# SCH_ZX-WiFi_2025-09-04.net
KiCad netlist of a schematic drawn in EasyEDA
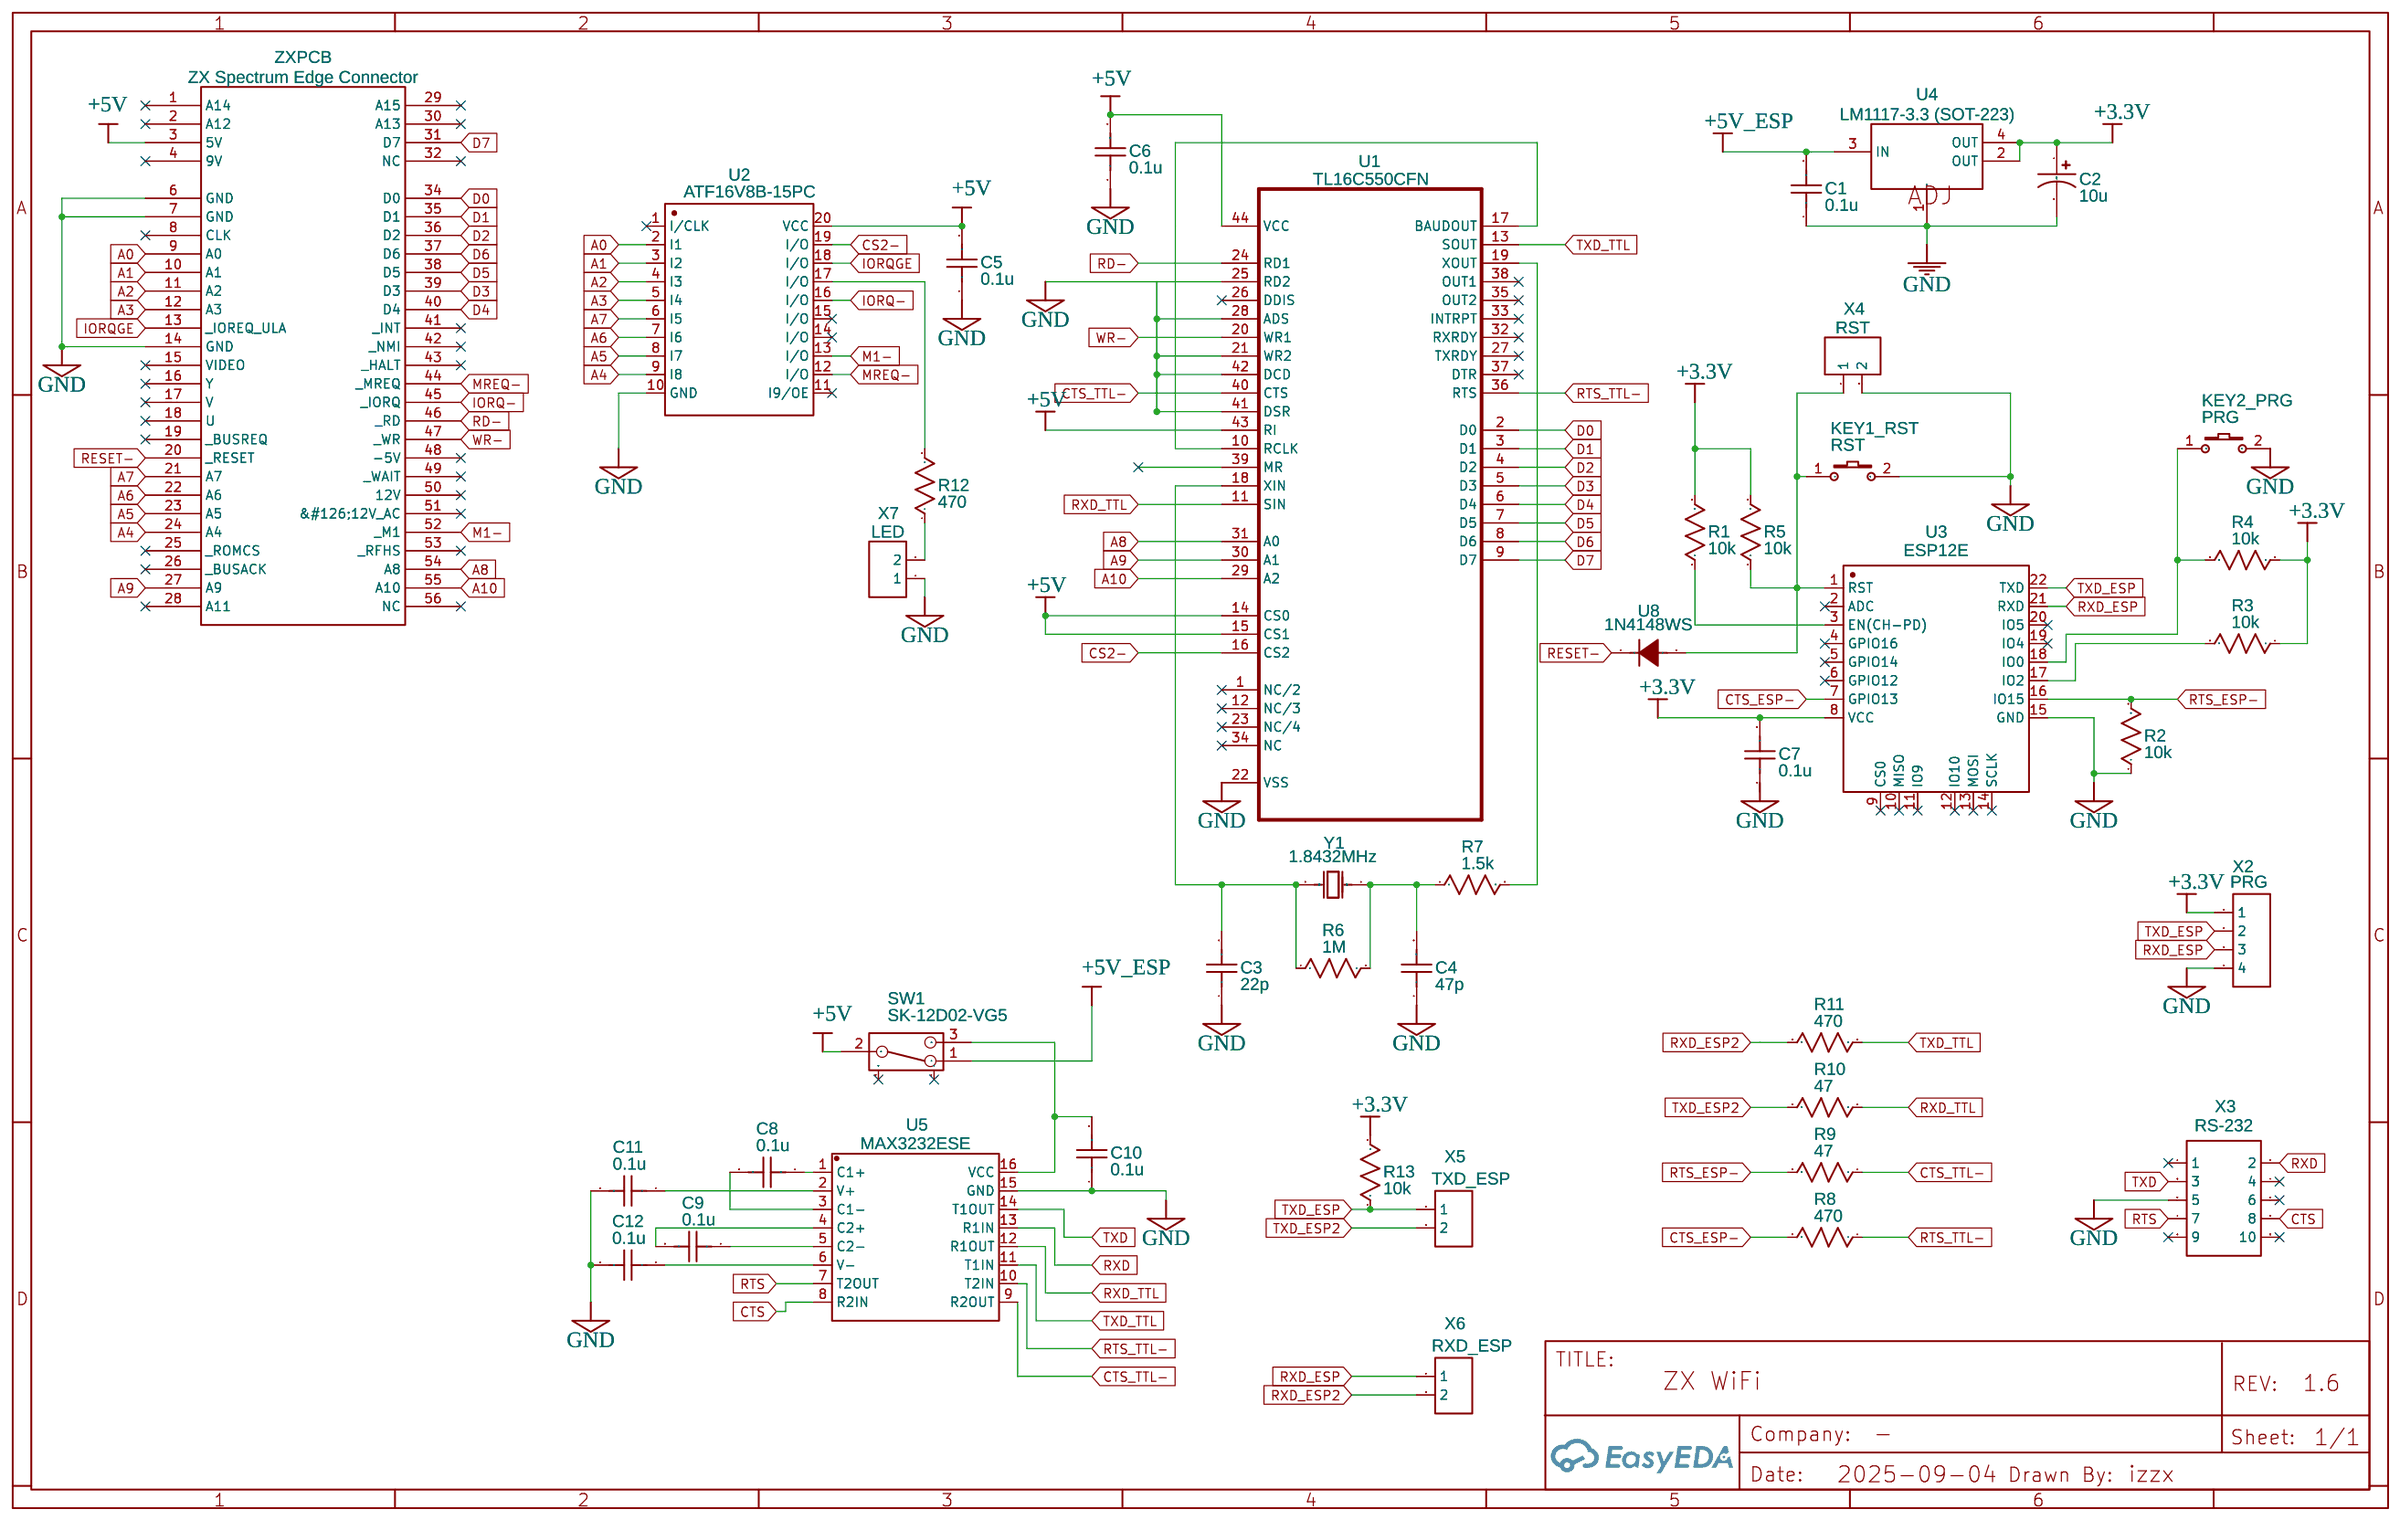
[diagram p0: schematic sheet]

(export (version "E")
  (design (tool "Eeschema 10.0.6"))
  (components
    (comp (ref "C1") (value "0.1u") (libsource (lib "") (part "C_0805_US_1")))
    (comp (ref "C2") (value "10u") (libsource (lib "") (part "C_Tan_SMD_A_US")))
    (comp (ref "C3") (value "22p") (libsource (lib "") (part "C_0805_US_1")))
    (comp (ref "C4") (value "47p") (libsource (lib "") (part "C_0805_US_1")))
    (comp (ref "C5") (value "0.1u") (libsource (lib "") (part "C_0805_US_1")))
    (comp (ref "C6") (value "0.1u") (libsource (lib "") (part "C_0805_US_1")))
    (comp (ref "C7") (value "0.1u") (libsource (lib "") (part "C_0805_US_1")))
    (comp (ref "C8") (value "0.1u") (libsource (lib "") (part "C_0805_US")))
    (comp (ref "C9") (value "0.1u") (libsource (lib "") (part "C_0805_US")))
    (comp (ref "C10") (value "0.1u") (libsource (lib "") (part "C_0805_US_1")))
    (comp (ref "C11") (value "0.1u") (libsource (lib "") (part "C_0805_US")))
    (comp (ref "C12") (value "0.1u") (libsource (lib "") (part "C_0805_US")))
    (comp (ref "KEY1_RST")
      (value "RST")
      (fields (field (name "Manufacturer Part") "K2-1107ST-A4SW-06"))
      (libsource (lib "") (part "K2-3.6×6.1_SMD"))
    )
    (comp (ref "KEY2_PRG")
      (value "PRG")
      (fields (field (name "Manufacturer Part") "K2-1107ST-A4SW-06"))
      (libsource (lib "") (part "K2-3.6×6.1_SMD_1"))
    )
    (comp (ref "R1") (value "10k") (libsource (lib "") (part "R_0805_US_1")))
    (comp (ref "R2") (value "10k") (libsource (lib "") (part "R_0805_US_1")))
    (comp (ref "R3") (value "10k") (libsource (lib "") (part "R_0805_US")))
    (comp (ref "R4") (value "10k") (libsource (lib "") (part "R_0805_US")))
    (comp (ref "R5") (value "10k") (libsource (lib "") (part "R_0805_US_1")))
    (comp (ref "R6") (value "1M") (libsource (lib "") (part "R_0805_US_2")))
    (comp (ref "R7") (value "1.5k") (libsource (lib "") (part "R_0805_US_2")))
    (comp (ref "R8") (value "470") (libsource (lib "") (part "R_0805_US")))
    (comp (ref "R9") (value "47") (libsource (lib "") (part "R_0805_US")))
    (comp (ref "R10") (value "47") (libsource (lib "") (part "R_0805_US")))
    (comp (ref "R11") (value "470") (libsource (lib "") (part "R_0805_US")))
    (comp (ref "R12") (value "470") (libsource (lib "") (part "R_0805_US_1")))
    (comp (ref "R13") (value "10k") (libsource (lib "") (part "R_0805_US_1")))
    (comp (ref "SW1")
      (value "SK-12D02-VG5")
      (fields (field (name "Manufacturer") "Rectangular Connectors - Contacts"))
      (libsource (lib "") (part "SK-12D02-VG5"))
    )
    (comp (ref "U1") (value "TL16C550CFN") (libsource (lib "") (part "TL16C550CFN")))
    (comp (ref "U2")
      (value "ATF16V8B-15PC")
      (fields
        (field (name "Manufacturer Part") "ATF16V8B-15PU")
        (field (name "Manufacturer") "MICROCHIP(美国微芯)")
      )
      (libsource (lib "") (part "ATF16V8B-15PU"))
    )
    (comp (ref "U3") (value "ESP12E") (libsource (lib "") (part "ESP12E/F")))
    (comp (ref "U4")
      (value "LM1117-3.3 (SOT-223)")
      (fields (field (name "Manufacturer Part") "LM317G-AA3-R") (field (name "Manufacturer") "UTC"))
      (libsource (lib "") (part "LM317(SOT-223)"))
    )
    (comp (ref "U5")
      (value "MAX3232ESE")
      (fields (field (name "Manufacturer") "UMW(友台半导体)"))
      (libsource (lib "") (part "MAX3232ESE"))
    )
    (comp (ref "U8")
      (value "1N4148WS")
      (fields (field (name "Manufacturer") "Zhengxin(正芯)"))
      (libsource (lib "") (part "1N4148WS"))
    )
    (comp (ref "X2") (value "PRG") (libsource (lib "") (part "HDR-M-2.54_1x4")))
    (comp (ref "X3") (value "RS-232") (libsource (lib "") (part "HDR-M-2.54_2x5")))
    (comp (ref "X4") (value "RST") (libsource (lib "") (part "HDR-M-2.54_1x2_1")))
    (comp (ref "X5") (value "TXD_ESP") (libsource (lib "") (part "HDR-F-2.54_1x2")))
    (comp (ref "X6") (value "RXD_ESP") (libsource (lib "") (part "HDR-F-2.54_1x2")))
    (comp (ref "X7") (value "LED") (libsource (lib "") (part "HDR-M-2.54_1x2")))
    (comp (ref "Y1")
      (value "1.8432MHz")
      (fields (field (name "Manufacturer Part") "X49UD3579MSD2SC") (field (name "Manufacturer") "ValuePro"))
      (libsource (lib "") (part "X49UD3579MSD2SC"))
    )
    (comp (ref "ZXPCB")
      (value "ZX Spectrum Edge Connector")
      (libsource (lib "") (part "ZX Spectrum Edge Connector"))
    )
  )
  (nets
    (net (code "1") (name "+3.3V") (class "Default")
      (node (ref "C2") (pin "1") (pinfunction "1_1") (pintype "unspecified"))
      (node (ref "C7") (pin "2") (pinfunction "2_2") (pintype "unspecified"))
      (node (ref "R1") (pin "2") (pinfunction "2_2") (pintype "unspecified"))
      (node (ref "R13") (pin "2") (pinfunction "2_2") (pintype "unspecified"))
      (node (ref "R3") (pin "1") (pinfunction "1_1") (pintype "unspecified"))
      (node (ref "R4") (pin "1") (pinfunction "1_1") (pintype "unspecified"))
      (node (ref "R5") (pin "2") (pinfunction "2_2") (pintype "unspecified"))
      (node (ref "U3") (pin "8") (pinfunction "VCC_8") (pintype "unspecified"))
      (node (ref "U4") (pin "2") (pinfunction "OUT_2") (pintype "passive"))
      (node (ref "U4") (pin "4") (pinfunction "OUT_4") (pintype "passive"))
      (node (ref "X2") (pin "1") (pinfunction "1_1") (pintype "unspecified"))
    )
    (net (code "2") (name "+5V") (class "Default")
      (node (ref "C5") (pin "2") (pinfunction "2_2") (pintype "unspecified"))
      (node (ref "C6") (pin "2") (pinfunction "2_2") (pintype "unspecified"))
      (node (ref "SW1") (pin "2") (pinfunction "2_2") (pintype "unspecified"))
      (node (ref "U1") (pin "14") (pinfunction "CS0_14") (pintype "input"))
      (node (ref "U1") (pin "15") (pinfunction "CS1_15") (pintype "input"))
      (node (ref "U1") (pin "43") (pinfunction "RI_43") (pintype "input"))
      (node (ref "U1") (pin "44") (pinfunction "VCC_44") (pintype "passive"))
      (node (ref "U2") (pin "20") (pinfunction "VCC_20") (pintype "unspecified"))
      (node (ref "ZXPCB") (pin "3") (pinfunction "5V_3") (pintype "unspecified"))
    )
    (net (code "3") (name "+5V_ESP") (class "Default")
      (node (ref "C1") (pin "2") (pinfunction "2_2") (pintype "unspecified"))
      (node (ref "SW1") (pin "1") (pinfunction "1_1") (pintype "unspecified"))
      (node (ref "U4") (pin "3") (pinfunction "IN_3") (pintype "passive"))
    )
    (net (code "4") (name "A0") (class "Default")
      (node (ref "U2") (pin "2") (pinfunction "I1_2") (pintype "unspecified"))
      (node (ref "ZXPCB") (pin "9") (pinfunction "A0_9") (pintype "unspecified"))
    )
    (net (code "5") (name "A1") (class "Default")
      (node (ref "U2") (pin "3") (pinfunction "I2_3") (pintype "unspecified"))
      (node (ref "ZXPCB") (pin "10") (pinfunction "A1_10") (pintype "unspecified"))
    )
    (net (code "6") (name "A2") (class "Default")
      (node (ref "U2") (pin "4") (pinfunction "I3_4") (pintype "unspecified"))
      (node (ref "ZXPCB") (pin "11") (pinfunction "A2_11") (pintype "unspecified"))
    )
    (net (code "7") (name "A3") (class "Default")
      (node (ref "U2") (pin "5") (pinfunction "I4_5") (pintype "unspecified"))
      (node (ref "ZXPCB") (pin "12") (pinfunction "A3_12") (pintype "unspecified"))
    )
    (net (code "8") (name "A4") (class "Default")
      (node (ref "U2") (pin "9") (pinfunction "I8_9") (pintype "unspecified"))
      (node (ref "ZXPCB") (pin "24") (pinfunction "A4_24") (pintype "unspecified"))
    )
    (net (code "9") (name "A5") (class "Default")
      (node (ref "U2") (pin "8") (pinfunction "I7_8") (pintype "unspecified"))
      (node (ref "ZXPCB") (pin "23") (pinfunction "A5_23") (pintype "unspecified"))
    )
    (net (code "10") (name "A6") (class "Default")
      (node (ref "U2") (pin "7") (pinfunction "I6_7") (pintype "unspecified"))
      (node (ref "ZXPCB") (pin "22") (pinfunction "A6_22") (pintype "unspecified"))
    )
    (net (code "11") (name "A7") (class "Default")
      (node (ref "U2") (pin "6") (pinfunction "I5_6") (pintype "unspecified"))
      (node (ref "ZXPCB") (pin "21") (pinfunction "A7_21") (pintype "unspecified"))
    )
    (net (code "12") (name "A8") (class "Default")
      (node (ref "U1") (pin "31") (pinfunction "A0_31") (pintype "input"))
      (node (ref "ZXPCB") (pin "54") (pinfunction "A8_54") (pintype "unspecified"))
    )
    (net (code "13") (name "A9") (class "Default")
      (node (ref "U1") (pin "30") (pinfunction "A1_30") (pintype "input"))
      (node (ref "ZXPCB") (pin "27") (pinfunction "A9_27") (pintype "unspecified"))
    )
    (net (code "14") (name "A10") (class "Default")
      (node (ref "U1") (pin "29") (pinfunction "A2_29") (pintype "input"))
      (node (ref "ZXPCB") (pin "55") (pinfunction "A10_55") (pintype "unspecified"))
    )
    (net (code "15") (name "CS2-") (class "Default")
      (node (ref "U1") (pin "16") (pinfunction "CS2_16") (pintype "input"))
      (node (ref "U2") (pin "19") (pinfunction "I/O_19") (pintype "unspecified"))
    )
    (net (code "16") (name "CTS") (class "Default")
      (node (ref "U5") (pin "8") (pinfunction "R2IN_8") (pintype "unspecified"))
      (node (ref "X3") (pin "8") (pinfunction "8_8") (pintype "unspecified"))
    )
    (net (code "17") (name "CTS_ESP-") (class "Default")
      (node (ref "R8") (pin "2") (pinfunction "2_2") (pintype "unspecified"))
      (node (ref "U3") (pin "7") (pinfunction "GPIO13_7") (pintype "unspecified"))
    )
    (net (code "18") (name "CTS_TTL-") (class "Default")
      (node (ref "R9") (pin "1") (pinfunction "1_1") (pintype "unspecified"))
      (node (ref "U1") (pin "40") (pinfunction "CTS_40") (pintype "input"))
      (node (ref "U5") (pin "9") (pinfunction "R2OUT_9") (pintype "unspecified"))
    )
    (net (code "19") (name "D0") (class "Default")
      (node (ref "U1") (pin "2") (pinfunction "D0_2") (pintype "unspecified"))
      (node (ref "ZXPCB") (pin "34") (pinfunction "D0_34") (pintype "unspecified"))
    )
    (net (code "20") (name "D1") (class "Default")
      (node (ref "U1") (pin "3") (pinfunction "D1_3") (pintype "unspecified"))
      (node (ref "ZXPCB") (pin "35") (pinfunction "D1_35") (pintype "unspecified"))
    )
    (net (code "21") (name "D2") (class "Default")
      (node (ref "U1") (pin "4") (pinfunction "D2_4") (pintype "unspecified"))
      (node (ref "ZXPCB") (pin "36") (pinfunction "D2_36") (pintype "unspecified"))
    )
    (net (code "22") (name "D3") (class "Default")
      (node (ref "U1") (pin "5") (pinfunction "D3_5") (pintype "unspecified"))
      (node (ref "ZXPCB") (pin "39") (pinfunction "D3_39") (pintype "unspecified"))
    )
    (net (code "23") (name "D4") (class "Default")
      (node (ref "U1") (pin "6") (pinfunction "D4_6") (pintype "unspecified"))
      (node (ref "ZXPCB") (pin "40") (pinfunction "D4_40") (pintype "unspecified"))
    )
    (net (code "24") (name "D5") (class "Default")
      (node (ref "U1") (pin "7") (pinfunction "D5_7") (pintype "unspecified"))
      (node (ref "ZXPCB") (pin "38") (pinfunction "D5_38") (pintype "unspecified"))
    )
    (net (code "25") (name "D6") (class "Default")
      (node (ref "U1") (pin "8") (pinfunction "D6_8") (pintype "unspecified"))
      (node (ref "ZXPCB") (pin "37") (pinfunction "D6_37") (pintype "unspecified"))
    )
    (net (code "26") (name "D7") (class "Default")
      (node (ref "U1") (pin "9") (pinfunction "D7_9") (pintype "unspecified"))
      (node (ref "ZXPCB") (pin "31") (pinfunction "D7_31") (pintype "unspecified"))
    )
    (net (code "27") (name "GND") (class "Default")
      (node (ref "C1") (pin "1") (pinfunction "1_1") (pintype "unspecified"))
      (node (ref "C10") (pin "1") (pinfunction "1_1") (pintype "unspecified"))
      (node (ref "C11") (pin "2") (pinfunction "2_2") (pintype "unspecified"))
      (node (ref "C12") (pin "2") (pinfunction "2_2") (pintype "unspecified"))
      (node (ref "C2") (pin "2") (pinfunction "2_2") (pintype "unspecified"))
      (node (ref "C3") (pin "1") (pinfunction "1_1") (pintype "unspecified"))
      (node (ref "C4") (pin "1") (pinfunction "1_1") (pintype "unspecified"))
      (node (ref "C5") (pin "1") (pinfunction "1_1") (pintype "unspecified"))
      (node (ref "C6") (pin "1") (pinfunction "1_1") (pintype "unspecified"))
      (node (ref "C7") (pin "1") (pinfunction "1_1") (pintype "unspecified"))
      (node (ref "KEY1_RST") (pin "2") (pinfunction "2_2") (pintype "unspecified"))
      (node (ref "KEY2_PRG") (pin "2") (pinfunction "2_2") (pintype "unspecified"))
      (node (ref "R2") (pin "1") (pinfunction "1_1") (pintype "unspecified"))
      (node (ref "U1") (pin "21") (pinfunction "WR2_21") (pintype "input"))
      (node (ref "U1") (pin "22") (pinfunction "VSS_22") (pintype "passive"))
      (node (ref "U1") (pin "25") (pinfunction "RD2_25") (pintype "input"))
      (node (ref "U1") (pin "28") (pinfunction "ADS_28") (pintype "input"))
      (node (ref "U1") (pin "41") (pinfunction "DSR_41") (pintype "input"))
      (node (ref "U1") (pin "42") (pinfunction "DCD_42") (pintype "input"))
      (node (ref "U2") (pin "10") (pinfunction "GND_10") (pintype "unspecified"))
      (node (ref "U3") (pin "15") (pinfunction "GND_15") (pintype "unspecified"))
      (node (ref "U4") (pin "1") (pinfunction "ADJ_1") (pintype "passive"))
      (node (ref "U5") (pin "15") (pinfunction "GND_15") (pintype "unspecified"))
      (node (ref "X2") (pin "4") (pinfunction "4_4") (pintype "unspecified"))
      (node (ref "X3") (pin "5") (pinfunction "5_5") (pintype "unspecified"))
      (node (ref "X4") (pin "2") (pinfunction "2_2") (pintype "unspecified"))
      (node (ref "X7") (pin "1") (pinfunction "1_1") (pintype "unspecified"))
      (node (ref "ZXPCB") (pin "14") (pinfunction "GND_14") (pintype "unspecified"))
      (node (ref "ZXPCB") (pin "6") (pinfunction "GND_6") (pintype "unspecified"))
      (node (ref "ZXPCB") (pin "7") (pinfunction "GND_7") (pintype "unspecified"))
    )
    (net (code "28") (name "IORQ-") (class "Default")
      (node (ref "U2") (pin "16") (pinfunction "I/O_16") (pintype "unspecified"))
      (node (ref "ZXPCB") (pin "45") (pinfunction "_IORQ_45") (pintype "unspecified"))
    )
    (net (code "29") (name "IORQGE") (class "Default")
      (node (ref "U2") (pin "18") (pinfunction "I/O_18") (pintype "unspecified"))
      (node (ref "ZXPCB") (pin "13") (pinfunction "_IOREQ_ULA_13") (pintype "unspecified"))
    )
    (net (code "30") (name "M1-") (class "Default")
      (node (ref "U2") (pin "13") (pinfunction "I/O_13") (pintype "unspecified"))
      (node (ref "ZXPCB") (pin "52") (pinfunction "_M1_52") (pintype "unspecified"))
    )
    (net (code "31") (name "MREQ-") (class "Default")
      (node (ref "U2") (pin "12") (pinfunction "I/O_12") (pintype "unspecified"))
      (node (ref "ZXPCB") (pin "44") (pinfunction "_MREQ_44") (pintype "unspecified"))
    )
    (net (code "32") (name "Net-(R12-Pad1)") (class "Default")
      (node (ref "R12") (pin "1") (pinfunction "1_1") (pintype "unspecified"))
      (node (ref "X7") (pin "2") (pinfunction "2_2") (pintype "unspecified"))
    )
    (net (code "33") (name "Net-(R12-Pad2)") (class "Default")
      (node (ref "R12") (pin "2") (pinfunction "2_2") (pintype "unspecified"))
      (node (ref "U2") (pin "17") (pinfunction "I/O_17") (pintype "unspecified"))
    )
    (net (code "34") (name "Net-(U1-BAUDOUT)") (class "Default")
      (node (ref "U1") (pin "10") (pinfunction "RCLK_10") (pintype "input"))
      (node (ref "U1") (pin "17") (pinfunction "BAUDOUT_17") (pintype "output"))
    )
    (net (code "35") (name "Net-(U1-XIN)") (class "Default")
      (node (ref "C3") (pin "2") (pinfunction "2_2") (pintype "unspecified"))
      (node (ref "R6") (pin "1") (pinfunction "1_1") (pintype "unspecified"))
      (node (ref "U1") (pin "18") (pinfunction "XIN_18") (pintype "input"))
      (node (ref "Y1") (pin "2") (pinfunction "OSC2_2") (pintype "input"))
    )
    (net (code "36") (name "Net-(U1-XOUT)") (class "Default")
      (node (ref "R7") (pin "2") (pinfunction "2_2") (pintype "unspecified"))
      (node (ref "U1") (pin "19") (pinfunction "XOUT_19") (pintype "output"))
    )
    (net (code "37") (name "Net-(U3-EN(CH-PD))") (class "Default")
      (node (ref "R1") (pin "1") (pinfunction "1_1") (pintype "unspecified"))
      (node (ref "U3") (pin "3") (pinfunction "EN(CH-PD)_3") (pintype "unspecified"))
    )
    (net (code "38") (name "Net-(U3-IO0)") (class "Default")
      (node (ref "KEY2_PRG") (pin "1") (pinfunction "1_1") (pintype "unspecified"))
      (node (ref "R4") (pin "2") (pinfunction "2_2") (pintype "unspecified"))
      (node (ref "U3") (pin "18") (pinfunction "IO0_18") (pintype "unspecified"))
    )
    (net (code "39") (name "Net-(U3-IO2)") (class "Default")
      (node (ref "R3") (pin "2") (pinfunction "2_2") (pintype "unspecified"))
      (node (ref "U3") (pin "17") (pinfunction "IO2_17") (pintype "unspecified"))
    )
    (net (code "40") (name "Net-(U3-RST)") (class "Default")
      (node (ref "KEY1_RST") (pin "1") (pinfunction "1_1") (pintype "unspecified"))
      (node (ref "R5") (pin "1") (pinfunction "1_1") (pintype "unspecified"))
      (node (ref "U3") (pin "1") (pinfunction "RST_1") (pintype "unspecified"))
      (node (ref "U8") (pin "2") (pinfunction "A_2") (pintype "unspecified"))
      (node (ref "X4") (pin "1") (pinfunction "1_1") (pintype "unspecified"))
    )
    (net (code "41") (name "Net-(U5-C1+)") (class "Default")
      (node (ref "C8") (pin "1") (pinfunction "1_1") (pintype "unspecified"))
      (node (ref "U5") (pin "1") (pinfunction "C1+_1") (pintype "unspecified"))
    )
    (net (code "42") (name "Net-(U5-C1-)") (class "Default")
      (node (ref "C8") (pin "2") (pinfunction "2_2") (pintype "unspecified"))
      (node (ref "U5") (pin "3") (pinfunction "C1-_3") (pintype "unspecified"))
    )
    (net (code "43") (name "Net-(U5-C2+)") (class "Default")
      (node (ref "C9") (pin "2") (pinfunction "2_2") (pintype "unspecified"))
      (node (ref "U5") (pin "4") (pinfunction "C2+_4") (pintype "unspecified"))
    )
    (net (code "44") (name "Net-(U5-C2-)") (class "Default")
      (node (ref "C9") (pin "1") (pinfunction "1_1") (pintype "unspecified"))
      (node (ref "U5") (pin "5") (pinfunction "C2-_5") (pintype "unspecified"))
    )
    (net (code "45") (name "Net-(U5-V+)") (class "Default")
      (node (ref "C11") (pin "1") (pinfunction "1_1") (pintype "unspecified"))
      (node (ref "U5") (pin "2") (pinfunction "V+_2") (pintype "unspecified"))
    )
    (net (code "46") (name "Net-(U5-V-)") (class "Default")
      (node (ref "C12") (pin "1") (pinfunction "1_1") (pintype "unspecified"))
      (node (ref "U5") (pin "6") (pinfunction "V-_6") (pintype "unspecified"))
    )
    (net (code "47") (name "Net-(U5-VCC)") (class "Default")
      (node (ref "C10") (pin "2") (pinfunction "2_2") (pintype "unspecified"))
      (node (ref "SW1") (pin "3") (pinfunction "3_3") (pintype "unspecified"))
      (node (ref "U5") (pin "16") (pinfunction "VCC_16") (pintype "unspecified"))
    )
    (net (code "48") (name "Net-(Y1-OSC1)") (class "Default")
      (node (ref "C4") (pin "2") (pinfunction "2_2") (pintype "unspecified"))
      (node (ref "R6") (pin "2") (pinfunction "2_2") (pintype "unspecified"))
      (node (ref "R7") (pin "1") (pinfunction "1_1") (pintype "unspecified"))
      (node (ref "Y1") (pin "1") (pinfunction "OSC1_1") (pintype "input"))
    )
    (net (code "49") (name "RD-") (class "Default")
      (node (ref "U1") (pin "24") (pinfunction "RD1_24") (pintype "input"))
      (node (ref "ZXPCB") (pin "46") (pinfunction "_RD_46") (pintype "unspecified"))
    )
    (net (code "50") (name "RESET-") (class "Default")
      (node (ref "U8") (pin "1") (pinfunction "K_1") (pintype "unspecified"))
      (node (ref "ZXPCB") (pin "20") (pinfunction "_RESET_20") (pintype "unspecified"))
    )
    (net (code "51") (name "RTS") (class "Default")
      (node (ref "U5") (pin "7") (pinfunction "T2OUT_7") (pintype "unspecified"))
      (node (ref "X3") (pin "7") (pinfunction "7_7") (pintype "unspecified"))
    )
    (net (code "52") (name "RTS_ESP-") (class "Default")
      (node (ref "R2") (pin "2") (pinfunction "2_2") (pintype "unspecified"))
      (node (ref "R9") (pin "2") (pinfunction "2_2") (pintype "unspecified"))
      (node (ref "U3") (pin "16") (pinfunction "IO15_16") (pintype "unspecified"))
    )
    (net (code "53") (name "RTS_TTL-") (class "Default")
      (node (ref "R8") (pin "1") (pinfunction "1_1") (pintype "unspecified"))
      (node (ref "U1") (pin "36") (pinfunction "RTS_36") (pintype "output"))
      (node (ref "U5") (pin "10") (pinfunction "T2IN_10") (pintype "unspecified"))
    )
    (net (code "54") (name "RXD") (class "Default")
      (node (ref "U5") (pin "13") (pinfunction "R1IN_13") (pintype "unspecified"))
      (node (ref "X3") (pin "2") (pinfunction "2_2") (pintype "unspecified"))
    )
    (net (code "55") (name "RXD_ESP") (class "Default")
      (node (ref "U3") (pin "21") (pinfunction "RXD_21") (pintype "unspecified"))
      (node (ref "X2") (pin "3") (pinfunction "3_3") (pintype "unspecified"))
      (node (ref "X6") (pin "1") (pinfunction "1_1") (pintype "input"))
    )
    (net (code "56") (name "RXD_ESP2") (class "Default")
      (node (ref "R11") (pin "2") (pinfunction "2_2") (pintype "unspecified"))
      (node (ref "X6") (pin "2") (pinfunction "2_2") (pintype "input"))
    )
    (net (code "57") (name "RXD_TTL") (class "Default")
      (node (ref "R10") (pin "1") (pinfunction "1_1") (pintype "unspecified"))
      (node (ref "U1") (pin "11") (pinfunction "SIN_11") (pintype "input"))
      (node (ref "U5") (pin "12") (pinfunction "R1OUT_12") (pintype "unspecified"))
    )
    (net (code "58") (name "TXD") (class "Default")
      (node (ref "U5") (pin "14") (pinfunction "T1OUT_14") (pintype "unspecified"))
      (node (ref "X3") (pin "3") (pinfunction "3_3") (pintype "unspecified"))
    )
    (net (code "59") (name "TXD_ESP") (class "Default")
      (node (ref "R13") (pin "1") (pinfunction "1_1") (pintype "unspecified"))
      (node (ref "U3") (pin "22") (pinfunction "TXD_22") (pintype "unspecified"))
      (node (ref "X2") (pin "2") (pinfunction "2_2") (pintype "unspecified"))
      (node (ref "X5") (pin "1") (pinfunction "1_1") (pintype "input"))
    )
    (net (code "60") (name "TXD_ESP2") (class "Default")
      (node (ref "R10") (pin "2") (pinfunction "2_2") (pintype "unspecified"))
      (node (ref "X5") (pin "2") (pinfunction "2_2") (pintype "input"))
    )
    (net (code "61") (name "TXD_TTL") (class "Default")
      (node (ref "R11") (pin "1") (pinfunction "1_1") (pintype "unspecified"))
      (node (ref "U1") (pin "13") (pinfunction "SOUT_13") (pintype "output"))
      (node (ref "U5") (pin "11") (pinfunction "T1IN_11") (pintype "unspecified"))
    )
    (net (code "62") (name "WR-") (class "Default")
      (node (ref "U1") (pin "20") (pinfunction "WR1_20") (pintype "input"))
      (node (ref "ZXPCB") (pin "47") (pinfunction "_WR_47") (pintype "unspecified"))
    )
    (net (code "63") (name "unconnected-(SW1-Pad4)") (class "Default")
      (node (ref "SW1") (pin "4") (pinfunction "4_4") (pintype "unspecified+no_connect"))
    )
    (net (code "64") (name "unconnected-(SW1-Pad5)") (class "Default")
      (node (ref "SW1") (pin "5") (pinfunction "5_5") (pintype "unspecified+no_connect"))
    )
    (net (code "65") (name "unconnected-(U1-DDIS-Pad26)") (class "Default")
      (node (ref "U1") (pin "26") (pinfunction "DDIS_26") (pintype "input+no_connect"))
    )
    (net (code "66") (name "unconnected-(U1-DTR-Pad37)") (class "Default")
      (node (ref "U1") (pin "37") (pinfunction "DTR_37") (pintype "output+no_connect"))
    )
    (net (code "67") (name "unconnected-(U1-INTRPT-Pad33)") (class "Default")
      (node (ref "U1") (pin "33") (pinfunction "INTRPT_33") (pintype "output+no_connect"))
    )
    (net (code "68") (name "unconnected-(U1-MR-Pad39)") (class "Default")
      (node (ref "U1") (pin "39") (pinfunction "MR_39") (pintype "input+no_connect"))
    )
    (net (code "69") (name "unconnected-(U1-NC-Pad34)") (class "Default")
      (node (ref "U1") (pin "34") (pinfunction "NC_34") (pintype "unspecified+no_connect"))
    )
    (net (code "70") (name "unconnected-(U1-NC{slash}2-Pad1)") (class "Default")
      (node (ref "U1") (pin "1") (pinfunction "NC/2_1") (pintype "unspecified+no_connect"))
    )
    (net (code "71") (name "unconnected-(U1-NC{slash}3-Pad12)") (class "Default")
      (node (ref "U1") (pin "12") (pinfunction "NC/3_12") (pintype "unspecified+no_connect"))
    )
    (net (code "72") (name "unconnected-(U1-NC{slash}4-Pad23)") (class "Default")
      (node (ref "U1") (pin "23") (pinfunction "NC/4_23") (pintype "unspecified+no_connect"))
    )
    (net (code "73") (name "unconnected-(U1-OUT1-Pad38)") (class "Default")
      (node (ref "U1") (pin "38") (pinfunction "OUT1_38") (pintype "output+no_connect"))
    )
    (net (code "74") (name "unconnected-(U1-OUT2-Pad35)") (class "Default")
      (node (ref "U1") (pin "35") (pinfunction "OUT2_35") (pintype "output+no_connect"))
    )
    (net (code "75") (name "unconnected-(U1-RXRDY-Pad32)") (class "Default")
      (node (ref "U1") (pin "32") (pinfunction "RXRDY_32") (pintype "output+no_connect"))
    )
    (net (code "76") (name "unconnected-(U1-TXRDY-Pad27)") (class "Default")
      (node (ref "U1") (pin "27") (pinfunction "TXRDY_27") (pintype "output+no_connect"))
    )
    (net (code "77") (name "unconnected-(U2-I9{slash}OE-Pad11)") (class "Default")
      (node (ref "U2") (pin "11") (pinfunction "I9/OE_11") (pintype "unspecified+no_connect"))
    )
    (net (code "78") (name "unconnected-(U2-I{slash}CLK-Pad1)") (class "Default")
      (node (ref "U2") (pin "1") (pinfunction "I/CLK_1") (pintype "unspecified+no_connect"))
    )
    (net (code "79") (name "unconnected-(U2-I{slash}O-Pad14)") (class "Default")
      (node (ref "U2") (pin "14") (pinfunction "I/O_14") (pintype "unspecified+no_connect"))
    )
    (net (code "80") (name "unconnected-(U2-I{slash}O-Pad15)") (class "Default")
      (node (ref "U2") (pin "15") (pinfunction "I/O_15") (pintype "unspecified+no_connect"))
    )
    (net (code "81") (name "unconnected-(U3-ADC-Pad2)") (class "Default")
      (node (ref "U3") (pin "2") (pinfunction "ADC_2") (pintype "unspecified+no_connect"))
    )
    (net (code "82") (name "unconnected-(U3-CS0-Pad9)") (class "Default")
      (node (ref "U3") (pin "9") (pinfunction "CS0_9") (pintype "unspecified+no_connect"))
    )
    (net (code "83") (name "unconnected-(U3-GPIO12-Pad6)") (class "Default")
      (node (ref "U3") (pin "6") (pinfunction "GPIO12_6") (pintype "unspecified+no_connect"))
    )
    (net (code "84") (name "unconnected-(U3-GPIO14-Pad5)") (class "Default")
      (node (ref "U3") (pin "5") (pinfunction "GPIO14_5") (pintype "unspecified+no_connect"))
    )
    (net (code "85") (name "unconnected-(U3-GPIO16-Pad4)") (class "Default")
      (node (ref "U3") (pin "4") (pinfunction "GPIO16_4") (pintype "unspecified+no_connect"))
    )
    (net (code "86") (name "unconnected-(U3-IO4-Pad19)") (class "Default")
      (node (ref "U3") (pin "19") (pinfunction "IO4_19") (pintype "unspecified+no_connect"))
    )
    (net (code "87") (name "unconnected-(U3-IO5-Pad20)") (class "Default")
      (node (ref "U3") (pin "20") (pinfunction "IO5_20") (pintype "unspecified+no_connect"))
    )
    (net (code "88") (name "unconnected-(U3-IO9-Pad11)") (class "Default")
      (node (ref "U3") (pin "11") (pinfunction "IO9_11") (pintype "unspecified+no_connect"))
    )
    (net (code "89") (name "unconnected-(U3-IO10-Pad12)") (class "Default")
      (node (ref "U3") (pin "12") (pinfunction "IO10_12") (pintype "unspecified+no_connect"))
    )
    (net (code "90") (name "unconnected-(U3-MISO-Pad10)") (class "Default")
      (node (ref "U3") (pin "10") (pinfunction "MISO_10") (pintype "unspecified+no_connect"))
    )
    (net (code "91") (name "unconnected-(U3-MOSI-Pad13)") (class "Default")
      (node (ref "U3") (pin "13") (pinfunction "MOSI_13") (pintype "unspecified+no_connect"))
    )
    (net (code "92") (name "unconnected-(U3-SCLK-Pad14)") (class "Default")
      (node (ref "U3") (pin "14") (pinfunction "SCLK_14") (pintype "unspecified+no_connect"))
    )
    (net (code "93") (name "unconnected-(X3-Pad1)") (class "Default")
      (node (ref "X3") (pin "1") (pinfunction "1_1") (pintype "unspecified+no_connect"))
    )
    (net (code "94") (name "unconnected-(X3-Pad4)") (class "Default")
      (node (ref "X3") (pin "4") (pinfunction "4_4") (pintype "unspecified+no_connect"))
    )
    (net (code "95") (name "unconnected-(X3-Pad6)") (class "Default")
      (node (ref "X3") (pin "6") (pinfunction "6_6") (pintype "unspecified+no_connect"))
    )
    (net (code "96") (name "unconnected-(X3-Pad9)") (class "Default")
      (node (ref "X3") (pin "9") (pinfunction "9_9") (pintype "unspecified+no_connect"))
    )
    (net (code "97") (name "unconnected-(X3-Pad10)") (class "Default")
      (node (ref "X3") (pin "10") (pinfunction "10_10") (pintype "unspecified+no_connect"))
    )
    (net (code "98") (name "unconnected-(ZXPCB-&#126;12V_AC-Pad51)") (class "Default")
      (node (ref "ZXPCB") (pin "51") (pinfunction "&#126;12V_AC_51") (pintype "unspecified+no_connect"))
    )
    (net (code "99") (name "unconnected-(ZXPCB--5V-Pad48)") (class "Default")
      (node (ref "ZXPCB") (pin "48") (pinfunction "-5V_48") (pintype "unspecified+no_connect"))
    )
    (net (code "100") (name "unconnected-(ZXPCB-9V-Pad4)") (class "Default")
      (node (ref "ZXPCB") (pin "4") (pinfunction "9V_4") (pintype "unspecified+no_connect"))
    )
    (net (code "101") (name "unconnected-(ZXPCB-12V-Pad50)") (class "Default")
      (node (ref "ZXPCB") (pin "50") (pinfunction "12V_50") (pintype "unspecified+no_connect"))
    )
    (net (code "102") (name "unconnected-(ZXPCB-A11-Pad28)") (class "Default")
      (node (ref "ZXPCB") (pin "28") (pinfunction "A11_28") (pintype "unspecified+no_connect"))
    )
    (net (code "103") (name "unconnected-(ZXPCB-A12-Pad2)") (class "Default")
      (node (ref "ZXPCB") (pin "2") (pinfunction "A12_2") (pintype "unspecified+no_connect"))
    )
    (net (code "104") (name "unconnected-(ZXPCB-A13-Pad30)") (class "Default")
      (node (ref "ZXPCB") (pin "30") (pinfunction "A13_30") (pintype "unspecified+no_connect"))
    )
    (net (code "105") (name "unconnected-(ZXPCB-A14-Pad1)") (class "Default")
      (node (ref "ZXPCB") (pin "1") (pinfunction "A14_1") (pintype "unspecified+no_connect"))
    )
    (net (code "106") (name "unconnected-(ZXPCB-A15-Pad29)") (class "Default")
      (node (ref "ZXPCB") (pin "29") (pinfunction "A15_29") (pintype "unspecified+no_connect"))
    )
    (net (code "107") (name "unconnected-(ZXPCB-CLK-Pad8)") (class "Default")
      (node (ref "ZXPCB") (pin "8") (pinfunction "CLK_8") (pintype "unspecified+no_connect"))
    )
    (net (code "108") (name "unconnected-(ZXPCB-NC-Pad32)") (class "Default")
      (node (ref "ZXPCB") (pin "32") (pinfunction "NC_32") (pintype "unspecified+no_connect"))
    )
    (net (code "109") (name "unconnected-(ZXPCB-NC-Pad56)") (class "Default")
      (node (ref "ZXPCB") (pin "56") (pinfunction "NC_56") (pintype "unspecified+no_connect"))
    )
    (net (code "110") (name "unconnected-(ZXPCB-U-Pad18)") (class "Default")
      (node (ref "ZXPCB") (pin "18") (pinfunction "U_18") (pintype "unspecified+no_connect"))
    )
    (net (code "111") (name "unconnected-(ZXPCB-V-Pad17)") (class "Default")
      (node (ref "ZXPCB") (pin "17") (pinfunction "V_17") (pintype "unspecified+no_connect"))
    )
    (net (code "112") (name "unconnected-(ZXPCB-VIDEO-Pad15)") (class "Default")
      (node (ref "ZXPCB") (pin "15") (pinfunction "VIDEO_15") (pintype "unspecified+no_connect"))
    )
    (net (code "113") (name "unconnected-(ZXPCB-Y-Pad16)") (class "Default")
      (node (ref "ZXPCB") (pin "16") (pinfunction "Y_16") (pintype "unspecified+no_connect"))
    )
    (net (code "114") (name "unconnected-(ZXPCB-_BUSACK-Pad26)") (class "Default")
      (node (ref "ZXPCB") (pin "26") (pinfunction "_BUSACK_26") (pintype "unspecified+no_connect"))
    )
    (net (code "115") (name "unconnected-(ZXPCB-_BUSREQ-Pad19)") (class "Default")
      (node (ref "ZXPCB") (pin "19") (pinfunction "_BUSREQ_19") (pintype "unspecified+no_connect"))
    )
    (net (code "116") (name "unconnected-(ZXPCB-_HALT-Pad43)") (class "Default")
      (node (ref "ZXPCB") (pin "43") (pinfunction "_HALT_43") (pintype "unspecified+no_connect"))
    )
    (net (code "117") (name "unconnected-(ZXPCB-_INT-Pad41)") (class "Default")
      (node (ref "ZXPCB") (pin "41") (pinfunction "_INT_41") (pintype "unspecified+no_connect"))
    )
    (net (code "118") (name "unconnected-(ZXPCB-_NMI-Pad42)") (class "Default")
      (node (ref "ZXPCB") (pin "42") (pinfunction "_NMI_42") (pintype "unspecified+no_connect"))
    )
    (net (code "119") (name "unconnected-(ZXPCB-_RFHS-Pad53)") (class "Default")
      (node (ref "ZXPCB") (pin "53") (pinfunction "_RFHS_53") (pintype "unspecified+no_connect"))
    )
    (net (code "120") (name "unconnected-(ZXPCB-_ROMCS-Pad25)") (class "Default")
      (node (ref "ZXPCB") (pin "25") (pinfunction "_ROMCS_25") (pintype "unspecified+no_connect"))
    )
    (net (code "121") (name "unconnected-(ZXPCB-_WAIT-Pad49)") (class "Default")
      (node (ref "ZXPCB") (pin "49") (pinfunction "_WAIT_49") (pintype "unspecified+no_connect"))
    )
  )
)
